# OvercurrentDetection.net
KiCad netlist of a schematic drawn in Altium Designer
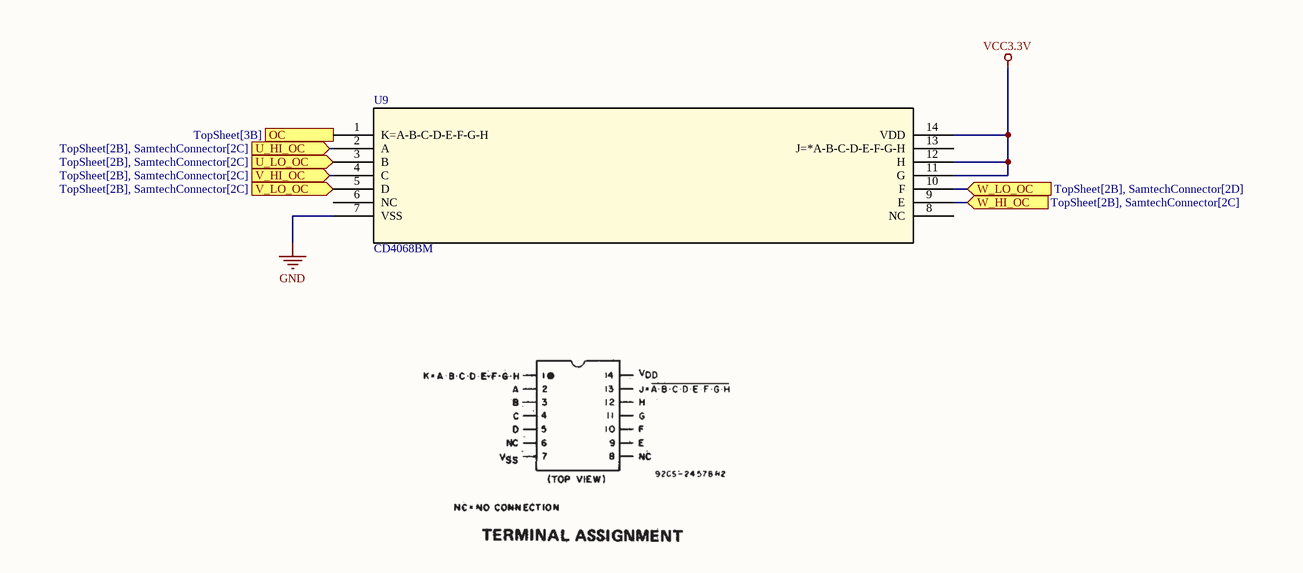
[diagram p0: OvercurrentDetection.SchDoc]

(export (version "E")
  (design (tool "Eeschema 10.0.6"))
  (components
    (comp (ref "U9")
      (value "CD4068BM")
      (footprint "D14")
      (description "No Description Available")
      (libsource (lib "HLU TUM") (part "CD4068BM"))
    )
  )
  (nets
    (net (code "1") (name "/OC") (class "Default")
      (node (ref "U9") (pin "1") (pinfunction "K=A-B-C-D-E-F-G-H_1") (pintype "passive"))
    )
    (net (code "2") (name "/U_HI_OC") (class "Default")
      (node (ref "U9") (pin "2") (pinfunction "A_2") (pintype "passive"))
    )
    (net (code "3") (name "/U_LO_OC") (class "Default")
      (node (ref "U9") (pin "3") (pinfunction "B_3") (pintype "passive"))
    )
    (net (code "4") (name "/V_HI_OC") (class "Default")
      (node (ref "U9") (pin "4") (pinfunction "C_4") (pintype "passive"))
    )
    (net (code "5") (name "/V_LO_OC") (class "Default")
      (node (ref "U9") (pin "5") (pinfunction "D_5") (pintype "passive"))
    )
    (net (code "6") (name "/W_HI_OC") (class "Default")
      (node (ref "U9") (pin "9") (pinfunction "E_9") (pintype "passive"))
    )
    (net (code "7") (name "/W_LO_OC") (class "Default")
      (node (ref "U9") (pin "10") (pinfunction "F_10") (pintype "passive"))
    )
    (net (code "8") (name "GND") (class "Default")
      (node (ref "U9") (pin "7") (pinfunction "VSS_7") (pintype "power_in"))
    )
    (net (code "9") (name "VCC3.3V") (class "Default")
      (node (ref "U9") (pin "11") (pinfunction "G_11") (pintype "passive"))
      (node (ref "U9") (pin "12") (pinfunction "H_12") (pintype "passive"))
      (node (ref "U9") (pin "14") (pinfunction "VDD_14") (pintype "power_in"))
    )
    (net (code "10") (name "unconnected-(U9-J=*A-B-C-D-E-F-G-H-Pad13)") (class "Default")
      (node (ref "U9") (pin "13") (pinfunction "J=*A-B-C-D-E-F-G-H_13") (pintype "passive"))
    )
    (net (code "11") (name "unconnected-(U9-NC-Pad6)") (class "Default")
      (node (ref "U9") (pin "6") (pinfunction "NC_6") (pintype "passive"))
    )
    (net (code "12") (name "unconnected-(U9-NC-Pad8)") (class "Default")
      (node (ref "U9") (pin "8") (pinfunction "NC_8") (pintype "passive"))
    )
  )
)
